# 60_RESISTANCE_FRONTEND.net
KiCad netlist of a schematic drawn in Altium Designer
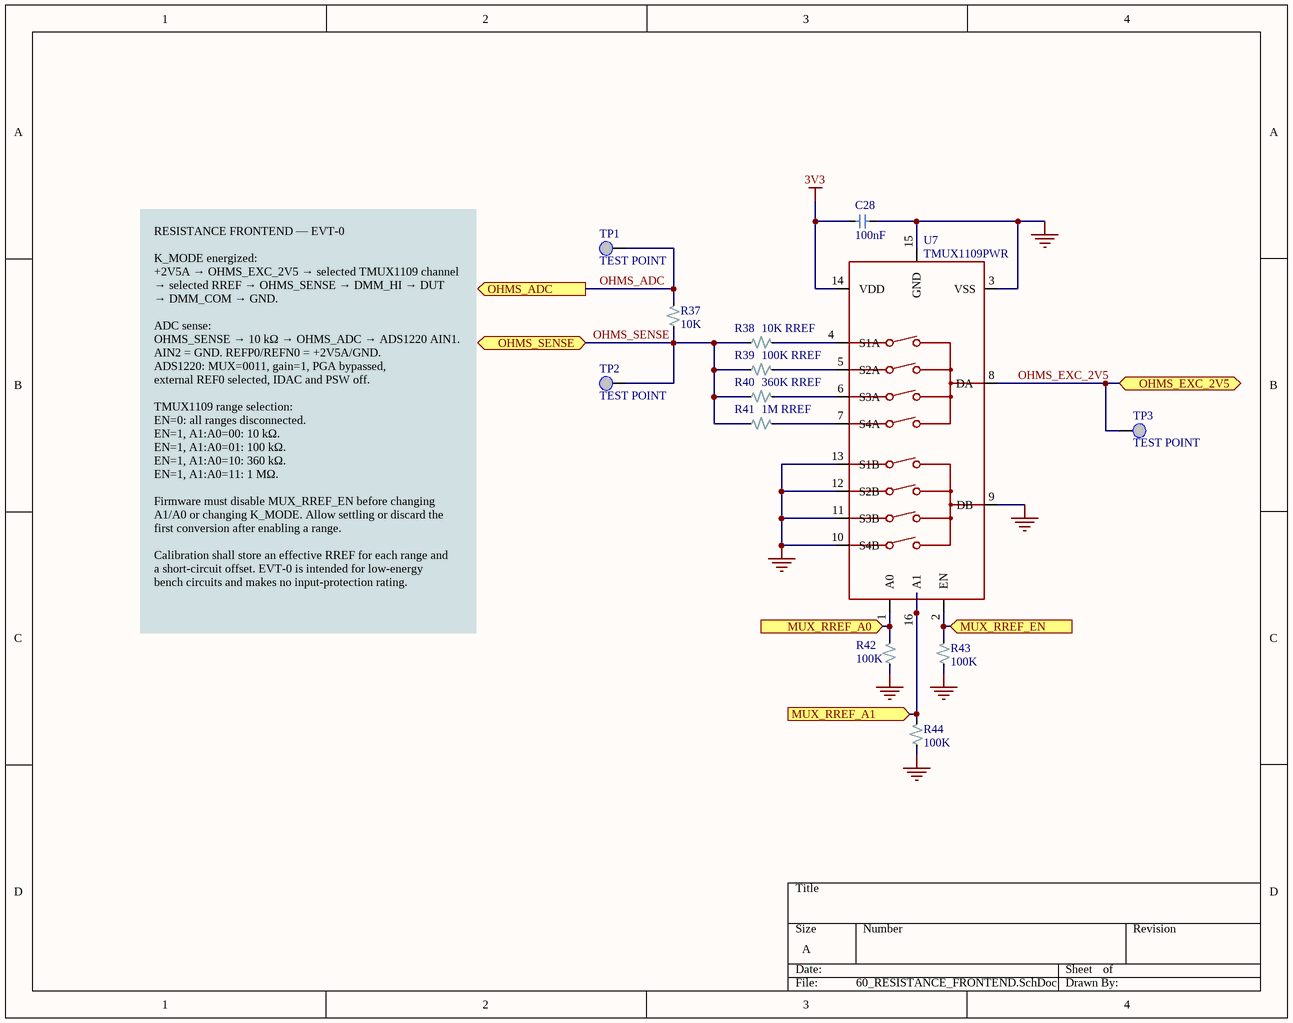
[diagram p0: 60_RESISTANCE_FRONTEND.SchDoc]

(export (version "E")
  (design (tool "Eeschema 10.0.6"))
  (components
    (comp (ref "C28")
      (value "100nF")
      (footprint "C0805")
      (libsource (lib "PocketLab_DMM_EVT0") (part "C_0805"))
    )
    (comp (ref "R37")
      (value "10K")
      (footprint "R0805")
      (description "RES 1/8W 0805")
      (fields
        (field (name "MANUFACTURER") "Stackpole Electronics")
        (field (name "MANUFACTURER PART NUMBER") "RNCF0805TKY10K0")
      )
      (libsource (lib "PocketLab_DMM_EVT0") (part "R_0805"))
    )
    (comp (ref "R38")
      (value "10K RREF")
      (footprint "R0805")
      (description "RES 1/8W 0805")
      (fields
        (field (name "MANUFACTURER") "Stackpole Electronics")
        (field (name "MANUFACTURER PART NUMBER") "RNCF0805TKY10K0")
      )
      (libsource (lib "PocketLab_DMM_EVT0") (part "R_0805"))
    )
    (comp (ref "R39")
      (value "100K RREF")
      (footprint "R0805")
      (description "RES 1/8W 0805")
      (fields
        (field (name "MANUFACTURER") "Stackpole Electronics")
        (field (name "MANUFACTURER PART NUMBER") "RNCF0805TKY10K0")
      )
      (libsource (lib "PocketLab_DMM_EVT0") (part "R_0805"))
    )
    (comp (ref "R40")
      (value "360K RREF")
      (footprint "R0805")
      (description "RES 1/8W 0805")
      (fields
        (field (name "MANUFACTURER") "Stackpole Electronics")
        (field (name "MANUFACTURER PART NUMBER") "RNCF0805TKY10K0")
      )
      (libsource (lib "PocketLab_DMM_EVT0") (part "R_0805"))
    )
    (comp (ref "R41")
      (value "1M RREF")
      (footprint "R0805")
      (description "RES 1/8W 0805")
      (fields
        (field (name "MANUFACTURER") "Stackpole Electronics")
        (field (name "MANUFACTURER PART NUMBER") "RNCF0805TKY10K0")
      )
      (libsource (lib "PocketLab_DMM_EVT0") (part "R_0805"))
    )
    (comp (ref "R42")
      (value "100K")
      (footprint "R0805")
      (description "RES 1/8W 0805")
      (fields
        (field (name "MANUFACTURER") "Stackpole Electronics")
        (field (name "MANUFACTURER PART NUMBER") "RNCF0805TKY10K0")
      )
      (libsource (lib "PocketLab_DMM_EVT0") (part "R_0805"))
    )
    (comp (ref "R43")
      (value "100K")
      (footprint "R0805")
      (description "RES 1/8W 0805")
      (fields
        (field (name "MANUFACTURER") "Stackpole Electronics")
        (field (name "MANUFACTURER PART NUMBER") "RNCF0805TKY10K0")
      )
      (libsource (lib "PocketLab_DMM_EVT0") (part "R_0805"))
    )
    (comp (ref "R44")
      (value "100K")
      (footprint "R0805")
      (description "RES 1/8W 0805")
      (fields
        (field (name "MANUFACTURER") "Stackpole Electronics")
        (field (name "MANUFACTURER PART NUMBER") "RNCF0805TKY10K0")
      )
      (libsource (lib "PocketLab_DMM_EVT0") (part "R_0805"))
    )
    (comp (ref "TP1")
      (value "TEST POINT")
      (footprint "TP_SMD_1P5MM")
      (description "SMD TEST POINT")
      (libsource (lib "PocketLab_DMM_EVT0") (part "TP_1.0MM"))
    )
    (comp (ref "TP2")
      (value "TEST POINT")
      (footprint "TP_SMD_1P5MM")
      (description "SMD TEST POINT")
      (libsource (lib "PocketLab_DMM_EVT0") (part "TP_1.0MM"))
    )
    (comp (ref "TP3")
      (value "TEST POINT")
      (footprint "TP_SMD_1P5MM")
      (description "SMD TEST POINT")
      (libsource (lib "PocketLab_DMM_EVT0") (part "TP_1.0MM"))
    )
    (comp (ref "U7")
      (value "TMUX1109PWR")
      (footprint "TMUX1109PWR")
      (description "4 4.9Ω Double Pole Four Throw (DP4T) TSSOP-16-175mil Analog Switches, Multiplexers ROHS")
      (fields (field (name "MANUFACTURER") "Texas Instruments"))
      (libsource (lib "PocketLab_DMM_EVT0") (part "TMUX1109PWR"))
    )
  )
  (nets
    (net (code "1") (name "/MUX_RREF_A0") (class "Default")
      (node (ref "R42") (pin "2") (pinfunction "2_2") (pintype "passive"))
      (node (ref "U7") (pin "1") (pinfunction "A0_1") (pintype "passive"))
    )
    (net (code "2") (name "/MUX_RREF_A1") (class "Default")
      (node (ref "R44") (pin "2") (pinfunction "2_2") (pintype "passive"))
      (node (ref "U7") (pin "16") (pinfunction "A1_16") (pintype "passive"))
    )
    (net (code "3") (name "/MUX_RREF_EN") (class "Default")
      (node (ref "R43") (pin "2") (pinfunction "2_2") (pintype "passive"))
      (node (ref "U7") (pin "2") (pinfunction "EN_2") (pintype "passive"))
    )
    (net (code "4") (name "/OHMS_ADC") (class "Default")
      (node (ref "R37") (pin "2") (pinfunction "2_2") (pintype "passive"))
      (node (ref "TP1") (pin "1") (pinfunction "1_1") (pintype "passive"))
    )
    (net (code "5") (name "/OHMS_EXC_2V5") (class "Default")
      (node (ref "TP3") (pin "1") (pinfunction "1_1") (pintype "passive"))
      (node (ref "U7") (pin "8") (pinfunction "DA_8") (pintype "passive"))
    )
    (net (code "6") (name "/OHMS_SENSE") (class "Default")
      (node (ref "R37") (pin "1") (pinfunction "1_1") (pintype "passive"))
      (node (ref "R38") (pin "1") (pinfunction "1_1") (pintype "passive"))
      (node (ref "R39") (pin "1") (pinfunction "1_1") (pintype "passive"))
      (node (ref "R40") (pin "1") (pinfunction "1_1") (pintype "passive"))
      (node (ref "R41") (pin "1") (pinfunction "1_1") (pintype "passive"))
      (node (ref "TP2") (pin "1") (pinfunction "1_1") (pintype "passive"))
    )
    (net (code "7") (name "3V3") (class "Default")
      (node (ref "C28") (pin "2") (pinfunction "2_2") (pintype "passive"))
      (node (ref "U7") (pin "14") (pinfunction "VDD_14") (pintype "passive"))
    )
    (net (code "8") (name "GND") (class "Default")
      (node (ref "C28") (pin "1") (pinfunction "1_1") (pintype "passive"))
      (node (ref "R42") (pin "1") (pinfunction "1_1") (pintype "passive"))
      (node (ref "R43") (pin "1") (pinfunction "1_1") (pintype "passive"))
      (node (ref "R44") (pin "1") (pinfunction "1_1") (pintype "passive"))
      (node (ref "U7") (pin "10") (pinfunction "S4B_10") (pintype "passive"))
      (node (ref "U7") (pin "11") (pinfunction "S3B_11") (pintype "passive"))
      (node (ref "U7") (pin "12") (pinfunction "S2B_12") (pintype "passive"))
      (node (ref "U7") (pin "13") (pinfunction "S1B_13") (pintype "passive"))
      (node (ref "U7") (pin "15") (pinfunction "GND_15") (pintype "passive"))
      (node (ref "U7") (pin "3") (pinfunction "VSS_3") (pintype "passive"))
      (node (ref "U7") (pin "9") (pinfunction "DB_9") (pintype "passive"))
    )
    (net (code "9") (name "Net-(U7-S1A)") (class "Default")
      (node (ref "R38") (pin "2") (pinfunction "2_2") (pintype "passive"))
      (node (ref "U7") (pin "4") (pinfunction "S1A_4") (pintype "passive"))
    )
    (net (code "10") (name "Net-(U7-S2A)") (class "Default")
      (node (ref "R39") (pin "2") (pinfunction "2_2") (pintype "passive"))
      (node (ref "U7") (pin "5") (pinfunction "S2A_5") (pintype "passive"))
    )
    (net (code "11") (name "Net-(U7-S3A)") (class "Default")
      (node (ref "R40") (pin "2") (pinfunction "2_2") (pintype "passive"))
      (node (ref "U7") (pin "6") (pinfunction "S3A_6") (pintype "passive"))
    )
    (net (code "12") (name "Net-(U7-S4A)") (class "Default")
      (node (ref "R41") (pin "2") (pinfunction "2_2") (pintype "passive"))
      (node (ref "U7") (pin "7") (pinfunction "S4A_7") (pintype "passive"))
    )
  )
)
